# power_board_24v.net
KiCad netlist of a schematic drawn in EasyEDA Pro
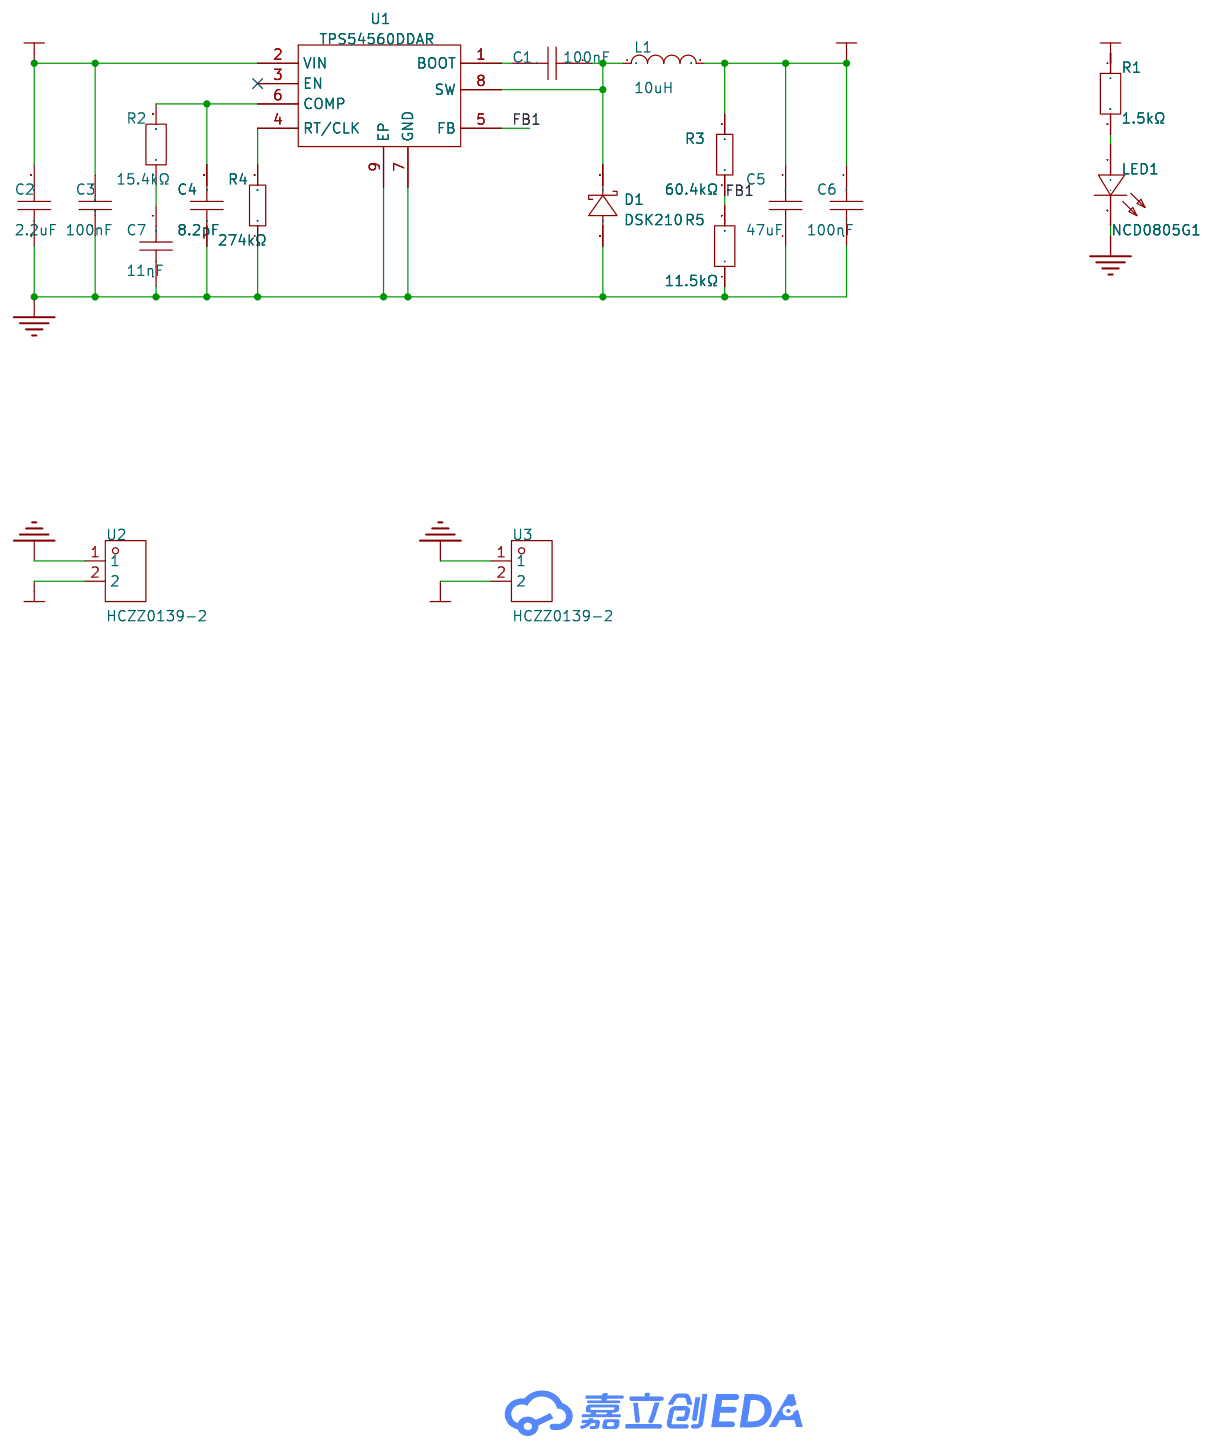
[diagram p0: schematic sheet]

(export (version "E")
  (design (tool "Eeschema 10.0.6"))
  (components
    (comp (ref "C1")
      (value "100nF")
      (footprint "easyedapro:C0603")
      (description "容值:100nF;精度:±10%;额定电压:50V;材质(温度系数):X7R;")
      (fields
        (field (name "Manufacturer Part") "CGA0603X7R104K500JT")
        (field (name "Manufacturer") "HRE(芯声)")
      )
      (libsource (lib "easyedapro") (part "CGA0603X7R104K500JT"))
    )
    (comp (ref "C2")
      (value "2.2uF")
      (fields
        (field (name "Manufacturer Part") "CL21A225KBQNNNE")
        (field (name "Manufacturer") "SAMSUNG(三星)")
      )
      (libsource (lib "easyedapro") (part "CC1206KKX7R0BB225"))
    )
    (comp (ref "C3")
      (value "100nF")
      (description "容值:100nF;精度:±10%;额定电压:50V;温度系数:X7R;")
      (fields
        (field (name "Manufacturer Part") "CGA0603X7R104K500JT")
        (field (name "Manufacturer") "HRE(芯声)")
      )
      (libsource (lib "easyedapro") (part "CL21B104KCFNNNE"))
    )
    (comp (ref "C4")
      (value "8.2pF")
      (footprint "easyedapro:C0603")
      (description "容值:8.2pF;额定电压:50V;材质(温度系数):C0G;")
      (fields
        (field (name "Manufacturer Part") "FCC0603N8R2C500CT")
        (field (name "Manufacturer") "FOJAN(富捷)")
      )
      (libsource (lib "easyedapro") (part "FCC0603N8R2C500CT"))
    )
    (comp (ref "C5")
      (value "47uF")
      (footprint "easyedapro:C0805")
      (description "容值:47uF;精度:±20%;额定电压:10V;材质(温度系数):X5R;")
      (fields
        (field (name "Manufacturer Part") "CGA0805X5R476M100MT")
        (field (name "Manufacturer") "HRE(芯声)")
      )
      (libsource (lib "easyedapro") (part "CGA0805X5R476M100MT"))
    )
    (comp (ref "C6")
      (value "100nF")
      (footprint "easyedapro:C0603")
      (description "容值:100nF;精度:±10%;额定电压:50V;材质(温度系数):X7R;")
      (fields
        (field (name "Manufacturer Part") "CGA0603X7R104K500JT")
        (field (name "Manufacturer") "HRE(芯声)")
      )
      (libsource (lib "easyedapro") (part "CGA0603X7R104K500JT"))
    )
    (comp (ref "C7")
      (value "11nF")
      (footprint "easyedapro:C0805")
      (description "容值:11nF;精度:±5%;额定电压:50V;材质(温度系数):C0G;")
      (fields
        (field (name "Manufacturer Part") "GRM2195C1H113JA01D")
        (field (name "Manufacturer") "muRata(村田)")
      )
      (libsource (lib "easyedapro") (part "GRM2195C1H113JA01D"))
    )
    (comp (ref "D1")
      (value "DSK210")
      (fields (field (name "Manufacturer") "宏迦橙"))
      (libsource (lib "easyedapro") (part "SS58_C18199168"))
    )
    (comp (ref "L1")
      (value "10uH")
      (fields
        (field (name "Manufacturer Part") "FHD252012S-100MT")
        (field (name "Manufacturer") "cjiang(长江微电)")
      )
      (libsource (lib "easyedapro") (part "PSPMAA0803H-100M-ANP"))
    )
    (comp (ref "LED1")
      (value "NCD0805G1")
      (fields (field (name "Manufacturer") "国星光电"))
      (libsource (lib "easyedapro") (part "FC-2012HRK-620D"))
    )
    (comp (ref "R1")
      (value "1.5kΩ")
      (fields
        (field (name "Manufacturer Part") "0603WAF1501T5E")
        (field (name "Manufacturer") "UNI-ROYAL(厚声)")
      )
      (libsource (lib "easyedapro") (part "FRC0603J151 TS"))
    )
    (comp (ref "R2")
      (value "15.4kΩ")
      (fields (field (name "Manufacturer Part") "RT0603BRD0715K4L") (field (name "Manufacturer") "YAGEO(国巨)"))
      (libsource (lib "easyedapro") (part "FRC0603F1542TS"))
    )
    (comp (ref "R3")
      (value "60.4kΩ")
      (footprint "easyedapro:R0603")
      (description "电阻类型:厚膜电阻;阻值:60.4kΩ;精度:±1%;功率:100mW;最大工作电压:75V;温度系数:±100ppm/°C;")
      (fields
        (field (name "Manufacturer Part") "0603WAF6042T5E")
        (field (name "Manufacturer") "UNI-ROYAL(厚声)")
      )
      (libsource (lib "easyedapro") (part "0603WAF6042T5E"))
    )
    (comp (ref "R4")
      (value "274kΩ")
      (footprint "easyedapro:R0603")
      (description "电阻类型:厚膜电阻;阻值:274kΩ;精度:±1%;功率:100mW;最大工作电压:75V;温度系数:±100ppm/°C;")
      (fields
        (field (name "Manufacturer Part") "0603WAF2743T5E")
        (field (name "Manufacturer") "UNI-ROYAL(厚声)")
      )
      (libsource (lib "easyedapro") (part "0603WAF2743T5E"))
    )
    (comp (ref "R5")
      (value "11.5kΩ")
      (footprint "easyedapro:R0603")
      (description "电阻类型:厚膜电阻;阻值:11.5kΩ;精度:±1%;功率:100mW;最大工作电压:75V;温度系数:±100ppm/°C;")
      (fields (field (name "Manufacturer Part") "FRC0603F1152TS") (field (name "Manufacturer") "FOJAN(富捷)"))
      (libsource (lib "easyedapro") (part "FRC0603F1152TS"))
    )
    (comp (ref "U1")
      (value "TPS54560DDAR")
      (footprint "easyedapro:SOIC-8_L5.0-W4.0-P1.27-LS6.0-BL-EP2.0")
      (description "功能类型:降压型;输出类型:可调;工作电压:4.5V~60V;输出电压:800mV~58.8V;输出电流:5A;")
      (fields (field (name "Manufacturer") "TI(德州仪器)"))
      (libsource (lib "easyedapro") (part "TPS54560DDAR"))
    )
    (comp (ref "U2")
      (value "HCZZ0139-2")
      (fields (field (name "Manufacturer") "HC(虹成电子)"))
      (libsource (lib "easyedapro") (part "ZX-XH2.54-2PZZ"))
    )
    (comp (ref "U3")
      (value "HCZZ0139-2")
      (footprint "easyedapro:CONN-TH_2P-P2.50_HCZZ0139-2")
      (fields (field (name "Manufacturer") "HC(虹成电子)"))
      (libsource (lib "easyedapro") (part "HCZZ0139-2"))
    )
  )
  (nets
    (net (code "1") (name "/FB1") (class "Default")
      (node (ref "R3") (pin "1") (pinfunction "1_1") (pintype "input"))
      (node (ref "R5") (pin "2") (pinfunction "2_2") (pintype "unspecified"))
      (node (ref "U1") (pin "5") (pinfunction "FB_5") (pintype "unspecified"))
    )
    (net (code "2") (name "5V") (class "Default")
      (node (ref "C5") (pin "2") (pinfunction "2_2") (pintype "unspecified"))
      (node (ref "C6") (pin "2") (pinfunction "2_2") (pintype "unspecified"))
      (node (ref "L1") (pin "2") (pinfunction "2_2") (pintype "unspecified"))
      (node (ref "R1") (pin "1") (pinfunction "1_1") (pintype "unspecified"))
      (node (ref "R3") (pin "2") (pinfunction "2_2") (pintype "input"))
      (node (ref "U3") (pin "2") (pinfunction "2_2") (pintype "unspecified"))
    )
    (net (code "3") (name "24V") (class "Default")
      (node (ref "C2") (pin "2") (pinfunction "2_2") (pintype "unspecified"))
      (node (ref "C3") (pin "2") (pinfunction "2_2") (pintype "input"))
      (node (ref "U1") (pin "2") (pinfunction "VIN_2") (pintype "unspecified"))
      (node (ref "U2") (pin "2") (pinfunction "2_2") (pintype "unspecified"))
    )
    (net (code "4") (name "GND") (class "Default")
      (node (ref "C2") (pin "1") (pinfunction "1_1") (pintype "unspecified"))
      (node (ref "C3") (pin "1") (pinfunction "1_1") (pintype "input"))
      (node (ref "C4") (pin "1") (pinfunction "1_1") (pintype "unspecified"))
      (node (ref "C5") (pin "1") (pinfunction "1_1") (pintype "unspecified"))
      (node (ref "C6") (pin "1") (pinfunction "1_1") (pintype "unspecified"))
      (node (ref "C7") (pin "1") (pinfunction "1_1") (pintype "unspecified"))
      (node (ref "D1") (pin "2") (pinfunction "A_2") (pintype "unspecified"))
      (node (ref "LED1") (pin "2") (pinfunction "-_2") (pintype "unspecified"))
      (node (ref "R4") (pin "1") (pinfunction "1_1") (pintype "input"))
      (node (ref "R5") (pin "1") (pinfunction "1_1") (pintype "unspecified"))
      (node (ref "U1") (pin "7") (pinfunction "GND_7") (pintype "unspecified"))
      (node (ref "U1") (pin "9") (pinfunction "EP_9") (pintype "unspecified"))
      (node (ref "U2") (pin "1") (pinfunction "1_1") (pintype "unspecified"))
      (node (ref "U3") (pin "1") (pinfunction "1_1") (pintype "unspecified"))
    )
    (net (code "5") (name "Net-(C7-Pad2)") (class "Default")
      (node (ref "C7") (pin "2") (pinfunction "2_2") (pintype "unspecified"))
      (node (ref "R2") (pin "1") (pinfunction "1_1") (pintype "unspecified"))
    )
    (net (code "6") (name "Net-(D1-K)") (class "Default")
      (node (ref "C1") (pin "2") (pinfunction "2_2") (pintype "unspecified"))
      (node (ref "D1") (pin "1") (pinfunction "K_1") (pintype "unspecified"))
      (node (ref "L1") (pin "1") (pinfunction "1_1") (pintype "unspecified"))
      (node (ref "U1") (pin "8") (pinfunction "SW_8") (pintype "unspecified"))
    )
    (net (code "7") (name "Net-(LED1-+)") (class "Default")
      (node (ref "LED1") (pin "1") (pinfunction "+_1") (pintype "unspecified"))
      (node (ref "R1") (pin "2") (pinfunction "2_2") (pintype "unspecified"))
    )
    (net (code "8") (name "Net-(U1-BOOT)") (class "Default")
      (node (ref "C1") (pin "1") (pinfunction "1_1") (pintype "unspecified"))
      (node (ref "U1") (pin "1") (pinfunction "BOOT_1") (pintype "unspecified"))
    )
    (net (code "9") (name "Net-(U1-COMP)") (class "Default")
      (node (ref "C4") (pin "2") (pinfunction "2_2") (pintype "unspecified"))
      (node (ref "R2") (pin "2") (pinfunction "2_2") (pintype "unspecified"))
      (node (ref "U1") (pin "6") (pinfunction "COMP_6") (pintype "unspecified"))
    )
    (net (code "10") (name "Net-(U1-RT{slash}CLK)") (class "Default")
      (node (ref "R4") (pin "2") (pinfunction "2_2") (pintype "input"))
      (node (ref "U1") (pin "4") (pinfunction "RT/CLK_4") (pintype "unspecified"))
    )
    (net (code "11") (name "unconnected-(U1-EN-Pad3)") (class "Default")
      (node (ref "U1") (pin "3") (pinfunction "EN_3") (pintype "unspecified+no_connect"))
    )
  )
)
